# shieldArduino.net
KiCad netlist of a schematic drawn in EAGLE
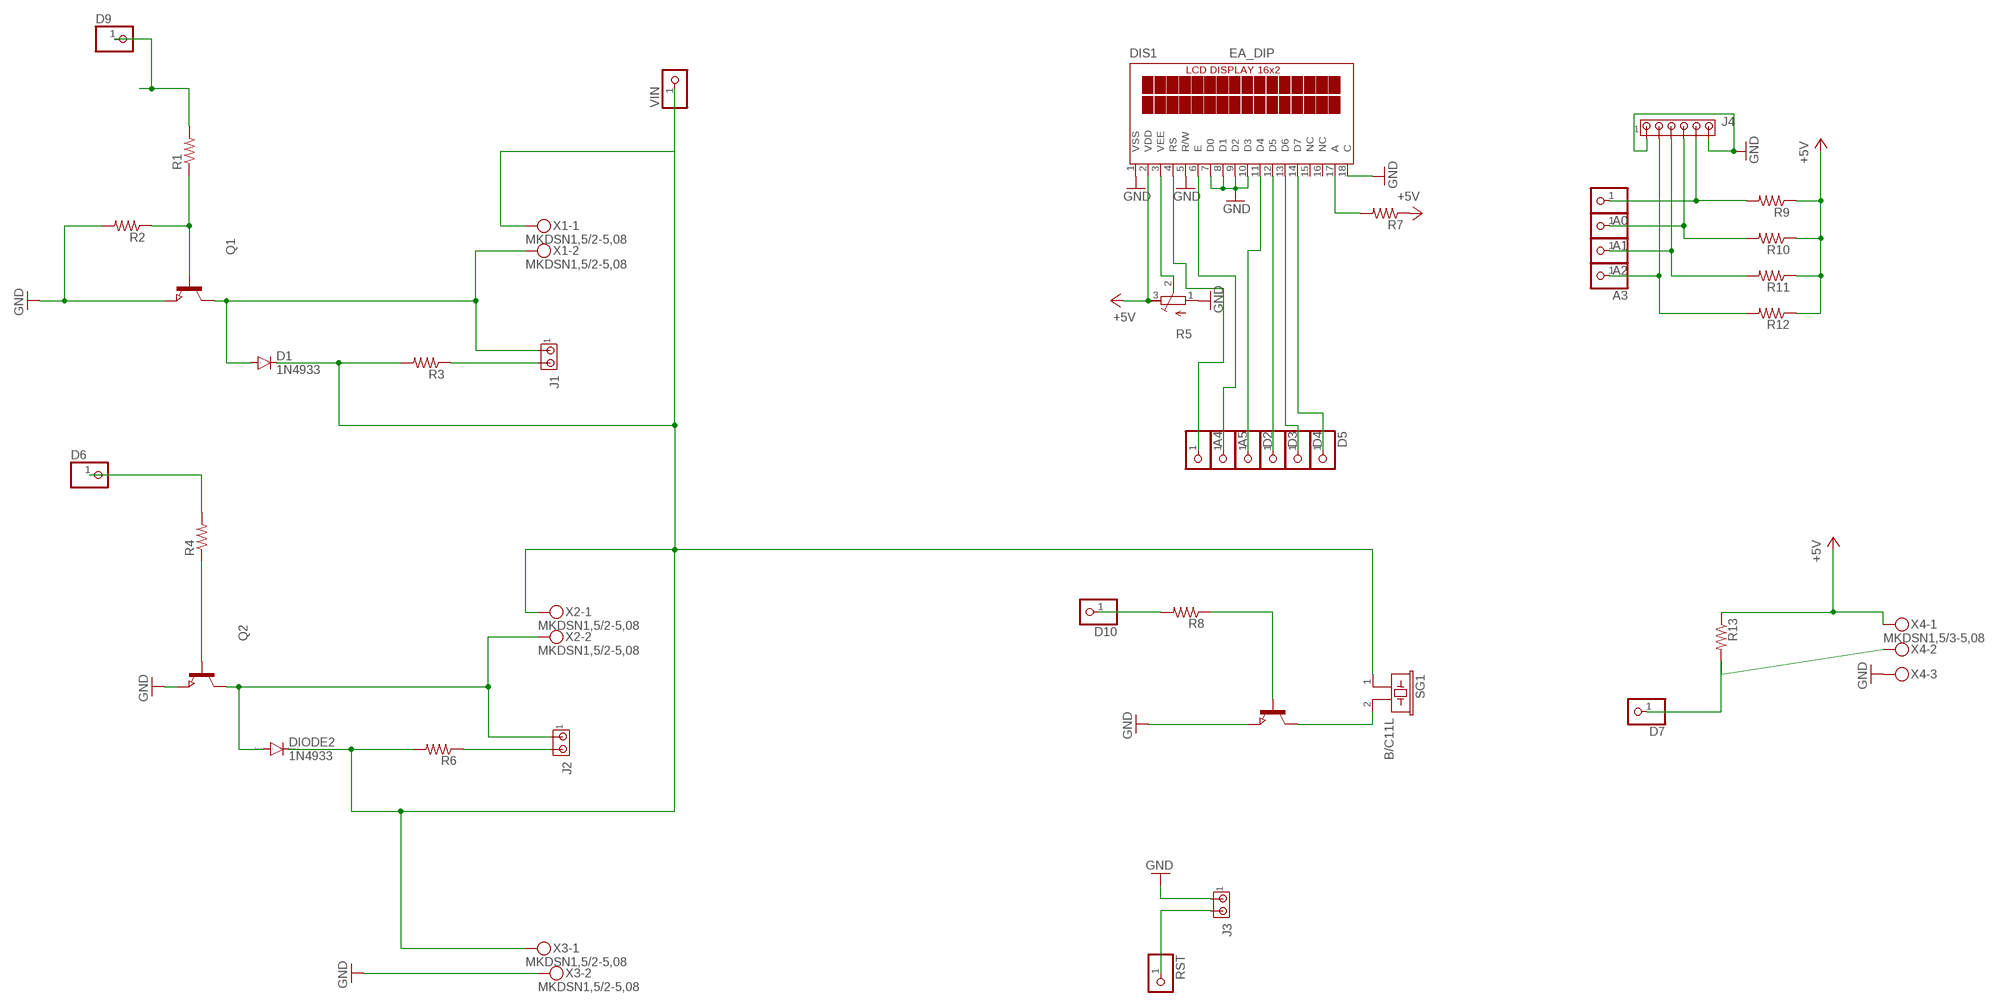
[diagram p0: schematic, sheet 1]

(export (version "E")
  (design (tool "Eeschema 10.0.6"))
  (components
    (comp (ref "A0")
      (value "PINHD-1X1")
      (footprint "eagle-import:1X01")
      (libsource (lib "eagle-import") (part "PINHD-1X1"))
    )
    (comp (ref "A1")
      (value "PINHD-1X1")
      (footprint "eagle-import:1X01")
      (libsource (lib "eagle-import") (part "PINHD-1X1"))
    )
    (comp (ref "A2")
      (value "PINHD-1X1")
      (footprint "eagle-import:1X01")
      (libsource (lib "eagle-import") (part "PINHD-1X1"))
    )
    (comp (ref "A3")
      (value "PINHD-1X1")
      (footprint "eagle-import:1X01")
      (libsource (lib "eagle-import") (part "PINHD-1X1"))
    )
    (comp (ref "A4")
      (value "PINHD-1X1")
      (footprint "eagle-import:1X01")
      (libsource (lib "eagle-import") (part "PINHD-1X1"))
    )
    (comp (ref "A5")
      (value "PINHD-1X1")
      (footprint "eagle-import:1X01")
      (libsource (lib "eagle-import") (part "PINHD-1X1"))
    )
    (comp (ref "D1")
      (value "1N4933")
      (footprint "eagle-import:DO41-10")
      (libsource (lib "eagle-import") (part "1N4933"))
    )
    (comp (ref "D2")
      (value "PINHD-1X1")
      (footprint "eagle-import:1X01")
      (libsource (lib "eagle-import") (part "PINHD-1X1"))
    )
    (comp (ref "D3")
      (value "PINHD-1X1")
      (footprint "eagle-import:1X01")
      (libsource (lib "eagle-import") (part "PINHD-1X1"))
    )
    (comp (ref "D4")
      (value "PINHD-1X1")
      (footprint "eagle-import:1X01")
      (libsource (lib "eagle-import") (part "PINHD-1X1"))
    )
    (comp (ref "D5")
      (value "PINHD-1X1")
      (footprint "eagle-import:1X01")
      (libsource (lib "eagle-import") (part "PINHD-1X1"))
    )
    (comp (ref "D6")
      (value "PINHD-1X1")
      (footprint "eagle-import:1X01")
      (libsource (lib "eagle-import") (part "PINHD-1X1"))
    )
    (comp (ref "D7")
      (value "PINHD-1X1")
      (footprint "eagle-import:1X01")
      (libsource (lib "eagle-import") (part "PINHD-1X1"))
    )
    (comp (ref "D9")
      (value "PINHD-1X1")
      (footprint "eagle-import:1X01")
      (libsource (lib "eagle-import") (part "PINHD-1X1"))
    )
    (comp (ref "D10")
      (value "PINHD-1X1")
      (footprint "eagle-import:1X01")
      (libsource (lib "eagle-import") (part "PINHD-1X1"))
    )
    (comp (ref "DIODE2")
      (value "1N4933")
      (footprint "eagle-import:DO41-10")
      (libsource (lib "eagle-import") (part "1N4933"))
    )
    (comp (ref "DIS1")
      (value "EA_DIP")
      (footprint "eagle-import:EA_DIP")
      (libsource (lib "eagle-import") (part "EA_DIP"))
    )
    (comp (ref "J1")
      (value "MTA02-156")
      (footprint "eagle-import:1X2MTA")
      (libsource (lib "eagle-import") (part "MTA02-156"))
    )
    (comp (ref "J2")
      (value "MTA02-156")
      (footprint "eagle-import:1X2MTA")
      (libsource (lib "eagle-import") (part "MTA02-156"))
    )
    (comp (ref "J3")
      (value "MTA02-156")
      (footprint "eagle-import:1X2MTA")
      (libsource (lib "eagle-import") (part "MTA02-156"))
    )
    (comp (ref "J4")
      (value "MTA06-156")
      (footprint "eagle-import:1X6MTA")
      (libsource (lib "eagle-import") (part "MTA06-156"))
    )
    (comp (ref "Q1")
      (value "NPN-TRANSISTOR_SOT23W")
      (footprint "eagle-import:SOT23W")
      (libsource (lib "eagle-import") (part "NPN-TRANSISTOR_SOT23W"))
    )
    (comp (ref "Q2")
      (value "NPN-TRANSISTOR_SOT23W")
      (footprint "eagle-import:SOT23W")
      (libsource (lib "eagle-import") (part "NPN-TRANSISTOR_SOT23W"))
    )
    (comp (ref "Q3")
      (value "NPN-TRANSISTOR_SOT23W")
      (footprint "eagle-import:SOT23W")
      (libsource (lib "eagle-import") (part "NPN-TRANSISTOR_SOT23W"))
    )
    (comp (ref "R1")
      (value "R-US_0617/22")
      (footprint "eagle-import:0617_22")
      (libsource (lib "eagle-import") (part "R-US_0617/22"))
    )
    (comp (ref "R2")
      (value "R-US_0617/22")
      (footprint "eagle-import:0617_22")
      (libsource (lib "eagle-import") (part "R-US_0617/22"))
    )
    (comp (ref "R3")
      (value "R-US_0617/22")
      (footprint "eagle-import:0617_22")
      (libsource (lib "eagle-import") (part "R-US_0617/22"))
    )
    (comp (ref "R4")
      (value "R-US_0617/22")
      (footprint "eagle-import:0617_22")
      (libsource (lib "eagle-import") (part "R-US_0617/22"))
    )
    (comp (ref "R5")
      (value "R-TRIMM3339P")
      (footprint "eagle-import:RTRIM3339P")
      (libsource (lib "eagle-import") (part "R-TRIMM3339P"))
    )
    (comp (ref "R6")
      (value "R-US_0617/22")
      (footprint "eagle-import:0617_22")
      (libsource (lib "eagle-import") (part "R-US_0617/22"))
    )
    (comp (ref "R7")
      (value "R-US_0617/22")
      (footprint "eagle-import:0617_22")
      (libsource (lib "eagle-import") (part "R-US_0617/22"))
    )
    (comp (ref "R8")
      (value "R-US_0617/22")
      (footprint "eagle-import:0617_22")
      (libsource (lib "eagle-import") (part "R-US_0617/22"))
    )
    (comp (ref "R9")
      (value "R-US_0617/22")
      (footprint "eagle-import:0617_22")
      (libsource (lib "eagle-import") (part "R-US_0617/22"))
    )
    (comp (ref "R10")
      (value "R-US_0617/22")
      (footprint "eagle-import:0617_22")
      (libsource (lib "eagle-import") (part "R-US_0617/22"))
    )
    (comp (ref "R11")
      (value "R-US_0617/22")
      (footprint "eagle-import:0617_22")
      (libsource (lib "eagle-import") (part "R-US_0617/22"))
    )
    (comp (ref "R12")
      (value "R-US_0617/22")
      (footprint "eagle-import:0617_22")
      (libsource (lib "eagle-import") (part "R-US_0617/22"))
    )
    (comp (ref "R13")
      (value "R-US_0617/22")
      (footprint "eagle-import:0617_22")
      (libsource (lib "eagle-import") (part "R-US_0617/22"))
    )
    (comp (ref "RST")
      (value "PINHD-1X1")
      (footprint "eagle-import:1X01")
      (libsource (lib "eagle-import") (part "PINHD-1X1"))
    )
    (comp (ref "SG1")
      (value "B/C11L")
      (footprint "eagle-import:B_C11L")
      (libsource (lib "eagle-import") (part "B/C11L"))
    )
    (comp (ref "VIN")
      (value "PINHD-1X1")
      (footprint "eagle-import:1X01")
      (libsource (lib "eagle-import") (part "PINHD-1X1"))
    )
    (comp (ref "X1")
      (value "MKDSN1,5/2-5,08")
      (footprint "eagle-import:MKDSN1,5_2-5,08")
      (libsource (lib "eagle-import") (part "MKDSN1,5/2-5,08"))
    )
    (comp (ref "X2")
      (value "MKDSN1,5/2-5,08")
      (footprint "eagle-import:MKDSN1,5_2-5,08")
      (libsource (lib "eagle-import") (part "MKDSN1,5/2-5,08"))
    )
    (comp (ref "X3")
      (value "MKDSN1,5/2-5,08")
      (footprint "eagle-import:MKDSN1,5_2-5,08")
      (libsource (lib "eagle-import") (part "MKDSN1,5/2-5,08"))
    )
    (comp (ref "X4")
      (value "MKDSN1,5/3-5,08")
      (footprint "eagle-import:MKDSN1,5_3-5,08")
      (libsource (lib "eagle-import") (part "MKDSN1,5/3-5,08"))
    )
  )
  (nets
    (net (code "1") (name "+5V") (class "Default")
      (node (ref "DIS1") (pin "2") (pinfunction "VDD_2") (pintype "power_in"))
      (node (ref "R10") (pin "1") (pinfunction "1_1") (pintype "passive"))
      (node (ref "R11") (pin "1") (pinfunction "1_1") (pintype "passive"))
      (node (ref "R12") (pin "1") (pinfunction "1_1") (pintype "passive"))
      (node (ref "R13") (pin "1") (pinfunction "1_1") (pintype "passive"))
      (node (ref "R5") (pin "3") (pinfunction "E_3") (pintype "passive"))
      (node (ref "R7") (pin "1") (pinfunction "1_1") (pintype "passive"))
      (node (ref "R9") (pin "1") (pinfunction "1_1") (pintype "passive"))
      (node (ref "X4") (pin "1") (pinfunction "KL_1") (pintype "passive"))
    )
    (net (code "2") (name "GND") (class "Default")
      (node (ref "DIS1") (pin "1") (pinfunction "VSS_1") (pintype "power_in"))
      (node (ref "DIS1") (pin "10") (pinfunction "D3_10") (pintype "input"))
      (node (ref "DIS1") (pin "18") (pinfunction "C_18") (pintype "passive"))
      (node (ref "DIS1") (pin "5") (pinfunction "R/W_5") (pintype "input"))
      (node (ref "DIS1") (pin "7") (pinfunction "D0_7") (pintype "input"))
      (node (ref "DIS1") (pin "8") (pinfunction "D1_8") (pintype "input"))
      (node (ref "DIS1") (pin "9") (pinfunction "D2_9") (pintype "input"))
      (node (ref "J3") (pin "1") (pinfunction "1_1") (pintype "passive"))
      (node (ref "J4") (pin "1") (pinfunction "1_1") (pintype "passive"))
      (node (ref "J4") (pin "6") (pinfunction "6_6") (pintype "passive"))
      (node (ref "Q1") (pin "3") (pinfunction "E_3") (pintype "passive"))
      (node (ref "Q2") (pin "3") (pinfunction "E_3") (pintype "passive"))
      (node (ref "Q3") (pin "3") (pinfunction "E_3") (pintype "passive"))
      (node (ref "R2") (pin "2") (pinfunction "2_2") (pintype "passive"))
      (node (ref "R5") (pin "1") (pinfunction "A_1") (pintype "passive"))
      (node (ref "X3") (pin "2") (pinfunction "KL_2") (pintype "passive"))
      (node (ref "X4") (pin "3") (pinfunction "KL_3") (pintype "passive"))
    )
    (net (code "3") (name "Net-(A0-Pad1)") (class "Default")
      (node (ref "A0") (pin "1") (pinfunction "1_1") (pintype "passive"))
      (node (ref "J4") (pin "5") (pinfunction "5_5") (pintype "passive"))
      (node (ref "R9") (pin "2") (pinfunction "2_2") (pintype "passive"))
    )
    (net (code "4") (name "Net-(A1-Pad1)") (class "Default")
      (node (ref "A1") (pin "1") (pinfunction "1_1") (pintype "passive"))
      (node (ref "J4") (pin "4") (pinfunction "4_4") (pintype "passive"))
      (node (ref "R10") (pin "2") (pinfunction "2_2") (pintype "passive"))
    )
    (net (code "5") (name "Net-(A2-Pad1)") (class "Default")
      (node (ref "A2") (pin "1") (pinfunction "1_1") (pintype "passive"))
      (node (ref "J4") (pin "3") (pinfunction "3_3") (pintype "passive"))
      (node (ref "R11") (pin "2") (pinfunction "2_2") (pintype "passive"))
    )
    (net (code "6") (name "Net-(A3-Pad1)") (class "Default")
      (node (ref "A3") (pin "1") (pinfunction "1_1") (pintype "passive"))
      (node (ref "J4") (pin "2") (pinfunction "2_2") (pintype "passive"))
      (node (ref "R12") (pin "2") (pinfunction "2_2") (pintype "passive"))
    )
    (net (code "7") (name "Net-(D6-Pad1)") (class "Default")
      (node (ref "D6") (pin "1") (pinfunction "1_1") (pintype "passive"))
      (node (ref "R4") (pin "2") (pinfunction "2_2") (pintype "passive"))
    )
    (net (code "8") (name "Net-(D9-Pad1)") (class "Default")
      (node (ref "D9") (pin "1") (pinfunction "1_1") (pintype "passive"))
      (node (ref "R1") (pin "2") (pinfunction "2_2") (pintype "passive"))
    )
    (net (code "9") (name "Net-(D10-Pad1)") (class "Default")
      (node (ref "D10") (pin "1") (pinfunction "1_1") (pintype "passive"))
      (node (ref "R8") (pin "2") (pinfunction "2_2") (pintype "passive"))
    )
    (net (code "10") (name "Net-(DIS1-A)") (class "Default")
      (node (ref "DIS1") (pin "17") (pinfunction "A_17") (pintype "passive"))
      (node (ref "R7") (pin "2") (pinfunction "2_2") (pintype "passive"))
    )
    (net (code "11") (name "Net-(DIS1-D4)") (class "Default")
      (node (ref "D2") (pin "1") (pinfunction "1_1") (pintype "passive"))
      (node (ref "DIS1") (pin "11") (pinfunction "D4_11") (pintype "input"))
    )
    (net (code "12") (name "Net-(DIS1-D5)") (class "Default")
      (node (ref "D3") (pin "1") (pinfunction "1_1") (pintype "passive"))
      (node (ref "DIS1") (pin "12") (pinfunction "D5_12") (pintype "input"))
    )
    (net (code "13") (name "Net-(DIS1-D6)") (class "Default")
      (node (ref "D4") (pin "1") (pinfunction "1_1") (pintype "passive"))
      (node (ref "DIS1") (pin "13") (pinfunction "D6_13") (pintype "input"))
    )
    (net (code "14") (name "Net-(DIS1-D7)") (class "Default")
      (node (ref "D5") (pin "1") (pinfunction "1_1") (pintype "passive"))
      (node (ref "DIS1") (pin "14") (pinfunction "D7_14") (pintype "input"))
    )
    (net (code "15") (name "Net-(DIS1-E)") (class "Default")
      (node (ref "A5") (pin "1") (pinfunction "1_1") (pintype "passive"))
      (node (ref "DIS1") (pin "6") (pinfunction "E_6") (pintype "input"))
    )
    (net (code "16") (name "Net-(DIS1-RS)") (class "Default")
      (node (ref "A4") (pin "1") (pinfunction "1_1") (pintype "passive"))
      (node (ref "DIS1") (pin "4") (pinfunction "RS_4") (pintype "input"))
    )
    (net (code "17") (name "Net-(DIS1-VEE)") (class "Default")
      (node (ref "DIS1") (pin "3") (pinfunction "VEE_3") (pintype "power_in"))
      (node (ref "R5") (pin "2") (pinfunction "S_2") (pintype "passive"))
    )
    (net (code "18") (name "Net-(J1-Pad2)") (class "Default")
      (node (ref "J1") (pin "2") (pinfunction "2_2") (pintype "passive"))
      (node (ref "R3") (pin "1") (pinfunction "1_1") (pintype "passive"))
    )
    (net (code "19") (name "Net-(J2-Pad2)") (class "Default")
      (node (ref "J2") (pin "2") (pinfunction "2_2") (pintype "passive"))
      (node (ref "R6") (pin "1") (pinfunction "1_1") (pintype "passive"))
    )
    (net (code "20") (name "Net-(J3-Pad2)") (class "Default")
      (node (ref "J3") (pin "2") (pinfunction "2_2") (pintype "passive"))
      (node (ref "RST") (pin "1") (pinfunction "1_1") (pintype "passive"))
    )
    (net (code "21") (name "Net-(Q1-B)") (class "Default")
      (node (ref "Q1") (pin "1") (pinfunction "B_1") (pintype "passive"))
      (node (ref "R1") (pin "1") (pinfunction "1_1") (pintype "passive"))
      (node (ref "R2") (pin "1") (pinfunction "1_1") (pintype "passive"))
    )
    (net (code "22") (name "Net-(Q1-C)") (class "Default")
      (node (ref "D1") (pin "A") (pinfunction "A_A") (pintype "passive"))
      (node (ref "J1") (pin "1") (pinfunction "1_1") (pintype "passive"))
      (node (ref "Q1") (pin "2") (pinfunction "C_2") (pintype "passive"))
      (node (ref "X1") (pin "2") (pinfunction "KL_2") (pintype "passive"))
    )
    (net (code "23") (name "Net-(Q2-B)") (class "Default")
      (node (ref "Q2") (pin "1") (pinfunction "B_1") (pintype "passive"))
      (node (ref "R4") (pin "1") (pinfunction "1_1") (pintype "passive"))
    )
    (net (code "24") (name "Net-(Q2-C)") (class "Default")
      (node (ref "DIODE2") (pin "A") (pinfunction "A_A") (pintype "passive"))
      (node (ref "J2") (pin "1") (pinfunction "1_1") (pintype "passive"))
      (node (ref "Q2") (pin "2") (pinfunction "C_2") (pintype "passive"))
      (node (ref "X2") (pin "2") (pinfunction "KL_2") (pintype "passive"))
    )
    (net (code "25") (name "Net-(Q3-B)") (class "Default")
      (node (ref "Q3") (pin "1") (pinfunction "B_1") (pintype "passive"))
      (node (ref "R8") (pin "1") (pinfunction "1_1") (pintype "passive"))
    )
    (net (code "26") (name "Net-(Q3-C)") (class "Default")
      (node (ref "Q3") (pin "2") (pinfunction "C_2") (pintype "passive"))
      (node (ref "SG1") (pin "2") (pinfunction "2_2") (pintype "passive"))
    )
    (net (code "27") (name "Net-(X1A-KL)") (class "Default")
      (node (ref "D1") (pin "C") (pinfunction "C_C") (pintype "passive"))
      (node (ref "DIODE2") (pin "C") (pinfunction "C_C") (pintype "passive"))
      (node (ref "R3") (pin "2") (pinfunction "2_2") (pintype "passive"))
      (node (ref "R6") (pin "2") (pinfunction "2_2") (pintype "passive"))
      (node (ref "SG1") (pin "1") (pinfunction "1_1") (pintype "passive"))
      (node (ref "VIN") (pin "1") (pinfunction "1_1") (pintype "passive"))
      (node (ref "X1") (pin "1") (pinfunction "KL_1") (pintype "passive"))
      (node (ref "X2") (pin "1") (pinfunction "KL_1") (pintype "passive"))
      (node (ref "X3") (pin "1") (pinfunction "KL_1") (pintype "passive"))
    )
    (net (code "28") (name "Net-(X4B-KL)") (class "Default")
      (node (ref "D7") (pin "1") (pinfunction "1_1") (pintype "passive"))
      (node (ref "R13") (pin "2") (pinfunction "2_2") (pintype "passive"))
      (node (ref "X4") (pin "2") (pinfunction "KL_2") (pintype "passive"))
    )
    (net (code "29") (name "unconnected-(DIS1-NC-Pad15)") (class "Default")
      (node (ref "DIS1") (pin "15") (pinfunction "NC_15") (pintype "no_connect"))
    )
    (net (code "30") (name "unconnected-(DIS1-NC-Pad16)") (class "Default")
      (node (ref "DIS1") (pin "16") (pinfunction "NC_16") (pintype "no_connect"))
    )
  )
)
